# ldr.net
KiCad netlist of a schematic drawn in EAGLE
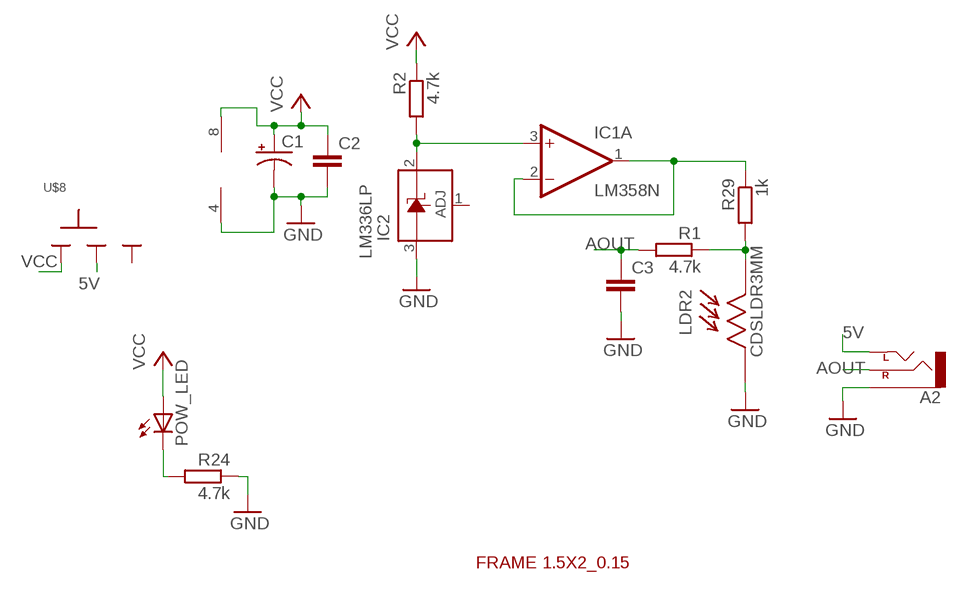
[diagram p0: schematic, sheet 1]

(export (version "E")
  (design (tool "Eeschema 10.0.6"))
  (components
    (comp (ref "A2")
      (value "AUX-CONNECTOR_CEDT_JANUARY_2015_V5_AUDIO-JACKPTH")
      (footprint "eagle-import:AUX-CONNECTOR_CEDT_JANUARY_2015_V5_AUDIO-JACK")
      (libsource (lib "eagle-import") (part "AUX-CONNECTOR_CEDT_JANUARY_2015_V5_AUDIO-JACKPTH"))
    )
    (comp (ref "C1")
      (value "CAP_POL")
      (footprint "eagle-import:E2,5-5-10U")
      (libsource (lib "eagle-import") (part "CAP_POL"))
    )
    (comp (ref "C2")
      (value "C-EU025-024X044")
      (footprint "eagle-import:C025-024X044")
      (libsource (lib "eagle-import") (part "C-EU025-024X044"))
    )
    (comp (ref "C3")
      (value "C-EU025-024X044")
      (footprint "eagle-import:C025-024X044")
      (libsource (lib "eagle-import") (part "C-EU025-024X044"))
    )
    (comp (ref "IC1")
      (value "LM358N")
      (footprint "eagle-import:DIL08")
      (libsource (lib "eagle-import") (part "LM358N"))
    )
    (comp (ref "IC2")
      (value "LM336LP")
      (footprint "eagle-import:TO92")
      (libsource (lib "eagle-import") (part "LM336LP"))
    )
    (comp (ref "LDR2")
      (value "CDSLDR3MM")
      (footprint "eagle-import:LDR3MM")
      (libsource (lib "eagle-import") (part "CDSLDR3MM"))
    )
    (comp (ref "POW_LED")
      (value "LED3MM")
      (footprint "eagle-import:LED3MM")
      (libsource (lib "eagle-import") (part "LED3MM"))
    )
    (comp (ref "R1")
      (value "4.7k")
      (footprint "eagle-import:0204_7")
      (libsource (lib "eagle-import") (part "R-EU_0204/7"))
    )
    (comp (ref "R2")
      (value "4.7k")
      (footprint "eagle-import:0204_7")
      (libsource (lib "eagle-import") (part "R-EU_0204/7"))
    )
    (comp (ref "R24")
      (value "4.7k")
      (footprint "eagle-import:0204_7")
      (libsource (lib "eagle-import") (part "R-EU_0204/7"))
    )
    (comp (ref "R29")
      (value "1k")
      (footprint "eagle-import:0204_7")
      (libsource (lib "eagle-import") (part "R-EU_0204/7"))
    )
    (comp (ref "U$1")
      (value "FRAME_1.5X2_RAD_0.15")
      (footprint "eagle-import:FRAME_1.5X2_RAD_0.15")
      (libsource (lib "eagle-import") (part "FRAME_1.5X2_RAD_0.15"))
    )
    (comp (ref "U$8")
      (value "SLIDESWITCH-BIG")
      (footprint "eagle-import:BIGSWITCH")
      (libsource (lib "eagle-import") (part "SLIDESWITCH-BIG"))
    )
  )
  (nets
    (net (code "1") (name "/5V") (class "Default")
      (node (ref "A2") (pin "TIP") (pinfunction "LEFT_TIP") (pintype "bidirectional"))
      (node (ref "U$8") (pin "2") (pinfunction "2_2") (pintype "bidirectional"))
    )
    (net (code "2") (name "/AOUT") (class "Default")
      (node (ref "A2") (pin "RING") (pinfunction "RIGHT_RING") (pintype "bidirectional"))
      (node (ref "C3") (pin "1") (pinfunction "1_1") (pintype "passive"))
      (node (ref "R1") (pin "2") (pinfunction "2_2") (pintype "passive"))
    )
    (net (code "3") (name "GND") (class "Default")
      (node (ref "A2") (pin "SLEEVE") (pinfunction "SLEEVE_SLEEVE") (pintype "bidirectional"))
      (node (ref "C1") (pin "-") (pinfunction "-_-") (pintype "passive"))
      (node (ref "C2") (pin "2") (pinfunction "2_2") (pintype "passive"))
      (node (ref "C3") (pin "2") (pinfunction "2_2") (pintype "passive"))
      (node (ref "IC1") (pin "4") (pinfunction "V-_4") (pintype "power_in"))
      (node (ref "IC2") (pin "3") (pinfunction "A_3") (pintype "input"))
      (node (ref "LDR2") (pin "P$2") (pinfunction "P$2_P$2") (pintype "bidirectional"))
      (node (ref "R24") (pin "1") (pinfunction "1_1") (pintype "passive"))
    )
    (net (code "4") (name "Net-(IC1A-+IN)") (class "Default")
      (node (ref "IC1") (pin "3") (pinfunction "+IN_3") (pintype "input"))
      (node (ref "IC2") (pin "2") (pinfunction "C_2") (pintype "passive"))
      (node (ref "R2") (pin "2") (pinfunction "2_2") (pintype "passive"))
    )
    (net (code "5") (name "Net-(IC1A--IN)") (class "Default")
      (node (ref "IC1") (pin "1") (pinfunction "OUT_1") (pintype "output"))
      (node (ref "IC1") (pin "2") (pinfunction "-IN_2") (pintype "input"))
      (node (ref "R29") (pin "1") (pinfunction "1_1") (pintype "passive"))
    )
    (net (code "6") (name "Net-(LDR2-PadP$1)") (class "Default")
      (node (ref "LDR2") (pin "P$1") (pinfunction "P$1_P$1") (pintype "bidirectional"))
      (node (ref "R1") (pin "1") (pinfunction "1_1") (pintype "passive"))
      (node (ref "R29") (pin "2") (pinfunction "2_2") (pintype "passive"))
    )
    (net (code "7") (name "Net-(POW_LED-C)") (class "Default")
      (node (ref "POW_LED") (pin "K") (pinfunction "C_K") (pintype "passive"))
      (node (ref "R24") (pin "2") (pinfunction "2_2") (pintype "passive"))
    )
    (net (code "8") (name "VCC") (class "Default")
      (node (ref "C1") (pin "+") (pinfunction "+_+") (pintype "passive"))
      (node (ref "C2") (pin "1") (pinfunction "1_1") (pintype "passive"))
      (node (ref "IC1") (pin "8") (pinfunction "V+_8") (pintype "power_in"))
      (node (ref "POW_LED") (pin "A") (pinfunction "A_A") (pintype "passive"))
      (node (ref "R2") (pin "1") (pinfunction "1_1") (pintype "passive"))
      (node (ref "U$8") (pin "1") (pinfunction "1_1") (pintype "bidirectional"))
    )
    (net (code "9") (name "unconnected-(IC2-ADJ-Pad1)") (class "Default")
      (node (ref "IC2") (pin "1") (pinfunction "ADJ_1") (pintype "input"))
    )
    (net (code "10") (name "unconnected-(U$8-Pad3)") (class "Default")
      (node (ref "U$8") (pin "3") (pinfunction "3_3") (pintype "bidirectional"))
    )
  )
)
